# STM32F050F_Base.net
KiCad netlist of a schematic drawn in EAGLE
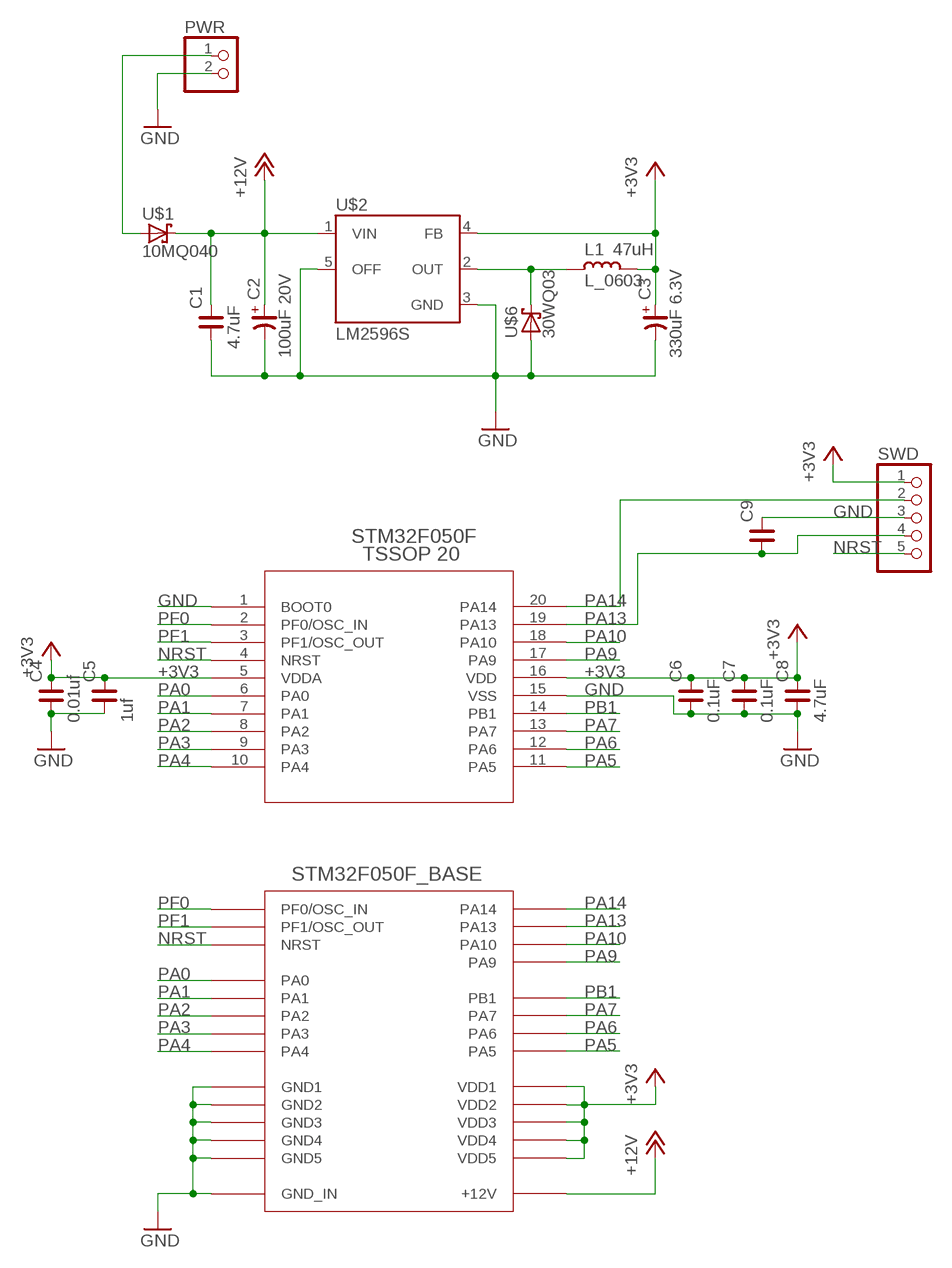
[diagram p0: schematic, sheet 1]

(export (version "E")
  (design (tool "Eeschema 10.0.6"))
  (components
    (comp (ref "C1")
      (value "4.7uF")
      (footprint "eagle-import:C1206")
      (libsource (lib "eagle-import") (part "C_1206"))
    )
    (comp (ref "C2")
      (value "100uF 20V")
      (footprint "eagle-import:C7343_T")
      (libsource (lib "eagle-import") (part "CP_7343"))
    )
    (comp (ref "C3")
      (value "330uF 6.3V")
      (footprint "eagle-import:C7343_T")
      (libsource (lib "eagle-import") (part "CP_7343"))
    )
    (comp (ref "C4")
      (value "0.01uf")
      (footprint "eagle-import:C0805")
      (libsource (lib "eagle-import") (part "C_0805"))
    )
    (comp (ref "C5")
      (value "1uf")
      (footprint "eagle-import:C0805")
      (libsource (lib "eagle-import") (part "C_0805"))
    )
    (comp (ref "C6")
      (value "0.1uF")
      (footprint "eagle-import:C0805")
      (libsource (lib "eagle-import") (part "C_0805"))
    )
    (comp (ref "C7")
      (value "0.1uF")
      (footprint "eagle-import:C0805")
      (libsource (lib "eagle-import") (part "C_0805"))
    )
    (comp (ref "C8")
      (value "4.7uF")
      (footprint "eagle-import:C1206")
      (libsource (lib "eagle-import") (part "C_1206"))
    )
    (comp (ref "C9")
      (value "C_1206")
      (footprint "eagle-import:C1206")
      (libsource (lib "eagle-import") (part "C_1206"))
    )
    (comp (ref "L1")
      (value "L_0603")
      (footprint "eagle-import:L0603")
      (fields (field (name "LCN0603T-47NJ-N") "47uH"))
      (libsource (lib "eagle-import") (part "L_0603"))
    )
    (comp (ref "PWR")
      (value "PINHD-1X02_2.54-90°-S")
      (footprint "eagle-import:1X02_90-S")
      (libsource (lib "eagle-import") (part "PINHD-1X02_2.54-90°-S"))
    )
    (comp (ref "SWD")
      (value "PINHD-1X05_2.54-90°-S")
      (footprint "eagle-import:1X05_90-S")
      (libsource (lib "eagle-import") (part "PINHD-1X05_2.54-90°-S"))
    )
    (comp (ref "U$1")
      (value "10MQ040")
      (footprint "eagle-import:SMA")
      (libsource (lib "eagle-import") (part "10MQ040"))
    )
    (comp (ref "U$2")
      (value "LM2596S")
      (footprint "eagle-import:TO263-5")
      (libsource (lib "eagle-import") (part "LM2596S"))
    )
    (comp (ref "U$4")
      (value "STM32F050F4P6")
      (footprint "eagle-import:TSSOP20")
      (libsource (lib "eagle-import") (part "STM32F050F4P6"))
    )
    (comp (ref "U$5")
      (value "STM32F050F_BASE_BASE")
      (footprint "eagle-import:STM32_BASE")
      (libsource (lib "eagle-import") (part "STM32F050F_BASE_BASE"))
    )
    (comp (ref "U$6")
      (value "30WQ03")
      (footprint "eagle-import:TO252")
      (libsource (lib "eagle-import") (part "30WQ03"))
    )
  )
  (nets
    (net (code "1") (name "+3V3") (class "Default")
      (node (ref "C3") (pin "+") (pinfunction "+_+") (pintype "passive"))
      (node (ref "C4") (pin "2") (pinfunction "2_2") (pintype "passive"))
      (node (ref "C5") (pin "2") (pinfunction "2_2") (pintype "passive"))
      (node (ref "C6") (pin "2") (pinfunction "2_2") (pintype "passive"))
      (node (ref "C7") (pin "2") (pinfunction "2_2") (pintype "passive"))
      (node (ref "C8") (pin "2") (pinfunction "2_2") (pintype "passive"))
      (node (ref "L1") (pin "1") (pinfunction "1_1") (pintype "passive"))
      (node (ref "SWD") (pin "1") (pinfunction "1_1") (pintype "passive"))
      (node (ref "U$2") (pin "4") (pinfunction "FB_4") (pintype "input"))
      (node (ref "U$4") (pin "16") (pinfunction "VDD_16") (pintype "passive"))
      (node (ref "U$4") (pin "5") (pinfunction "VDDA_5") (pintype "passive"))
      (node (ref "U$5") (pin "VDD1") (pinfunction "VDD1_VDD1") (pintype "passive"))
      (node (ref "U$5") (pin "VDD2") (pinfunction "VDD2_VDD2") (pintype "passive"))
      (node (ref "U$5") (pin "VDD3") (pinfunction "VDD3_VDD3") (pintype "passive"))
      (node (ref "U$5") (pin "VDD4") (pinfunction "VDD4_VDD4") (pintype "passive"))
      (node (ref "U$5") (pin "VDD5") (pinfunction "VDD5_VDD5") (pintype "passive"))
    )
    (net (code "2") (name "+12V") (class "Default")
      (node (ref "C1") (pin "2") (pinfunction "2_2") (pintype "passive"))
      (node (ref "C2") (pin "+") (pinfunction "+_+") (pintype "passive"))
      (node (ref "U$1") (pin "C") (pinfunction "C_C") (pintype "passive"))
      (node (ref "U$2") (pin "1") (pinfunction "VIN_1") (pintype "power_in"))
      (node (ref "U$5") (pin "+12V") (pinfunction "+12V_+12V") (pintype "passive"))
    )
    (net (code "3") (name "/NRST") (class "Default")
      (node (ref "SWD") (pin "5") (pinfunction "5_5") (pintype "passive"))
      (node (ref "U$4") (pin "4") (pinfunction "NRST_4") (pintype "passive"))
      (node (ref "U$5") (pin "NRST") (pinfunction "NRST_NRST") (pintype "passive"))
    )
    (net (code "4") (name "/PA0") (class "Default")
      (node (ref "U$4") (pin "6") (pinfunction "PA0_6") (pintype "passive"))
      (node (ref "U$5") (pin "PA0") (pinfunction "PA0_PA0") (pintype "passive"))
    )
    (net (code "5") (name "/PA1") (class "Default")
      (node (ref "U$4") (pin "7") (pinfunction "PA1_7") (pintype "passive"))
      (node (ref "U$5") (pin "PA1") (pinfunction "PA1_PA1") (pintype "passive"))
    )
    (net (code "6") (name "/PA2") (class "Default")
      (node (ref "U$4") (pin "8") (pinfunction "PA2_8") (pintype "passive"))
      (node (ref "U$5") (pin "PA2") (pinfunction "PA2_PA2") (pintype "passive"))
    )
    (net (code "7") (name "/PA3") (class "Default")
      (node (ref "U$4") (pin "9") (pinfunction "PA3_9") (pintype "passive"))
      (node (ref "U$5") (pin "PA3") (pinfunction "PA3_PA3") (pintype "passive"))
    )
    (net (code "8") (name "/PA4") (class "Default")
      (node (ref "U$4") (pin "10") (pinfunction "PA4_10") (pintype "passive"))
      (node (ref "U$5") (pin "PA4") (pinfunction "PA4_PA4") (pintype "passive"))
    )
    (net (code "9") (name "/PA5") (class "Default")
      (node (ref "U$4") (pin "11") (pinfunction "PA5_11") (pintype "passive"))
      (node (ref "U$5") (pin "PA5") (pinfunction "PA5_PA5") (pintype "passive"))
    )
    (net (code "10") (name "/PA6") (class "Default")
      (node (ref "U$4") (pin "12") (pinfunction "PA6_12") (pintype "passive"))
      (node (ref "U$5") (pin "PA6") (pinfunction "PA6_PA6") (pintype "passive"))
    )
    (net (code "11") (name "/PA7") (class "Default")
      (node (ref "U$4") (pin "13") (pinfunction "PA7_13") (pintype "passive"))
      (node (ref "U$5") (pin "PA7") (pinfunction "PA7_PA7") (pintype "passive"))
    )
    (net (code "12") (name "/PA9") (class "Default")
      (node (ref "U$4") (pin "17") (pinfunction "PA9_17") (pintype "passive"))
      (node (ref "U$5") (pin "PA9") (pinfunction "PA9_PA9") (pintype "passive"))
    )
    (net (code "13") (name "/PA10") (class "Default")
      (node (ref "U$4") (pin "18") (pinfunction "PA10_18") (pintype "passive"))
      (node (ref "U$5") (pin "PA10") (pinfunction "PA10_PA10") (pintype "passive"))
    )
    (net (code "14") (name "/PA13") (class "Default")
      (node (ref "C9") (pin "1") (pinfunction "1_1") (pintype "passive"))
      (node (ref "SWD") (pin "4") (pinfunction "4_4") (pintype "passive"))
      (node (ref "U$4") (pin "19") (pinfunction "PA13_19") (pintype "passive"))
      (node (ref "U$5") (pin "PA13") (pinfunction "PA13_PA13") (pintype "passive"))
    )
    (net (code "15") (name "/PA14") (class "Default")
      (node (ref "SWD") (pin "2") (pinfunction "2_2") (pintype "passive"))
      (node (ref "U$4") (pin "20") (pinfunction "PA14_20") (pintype "passive"))
      (node (ref "U$5") (pin "PA14") (pinfunction "PA14_PA14") (pintype "passive"))
    )
    (net (code "16") (name "/PB1") (class "Default")
      (node (ref "U$4") (pin "14") (pinfunction "PB1_14") (pintype "passive"))
      (node (ref "U$5") (pin "PB1") (pinfunction "PB1_PB1") (pintype "passive"))
    )
    (net (code "17") (name "/PF0") (class "Default")
      (node (ref "U$4") (pin "2") (pinfunction "PF0/OSC_IN_2") (pintype "passive"))
      (node (ref "U$5") (pin "PF0") (pinfunction "PF0/OSC_IN_PF0") (pintype "passive"))
    )
    (net (code "18") (name "/PF1") (class "Default")
      (node (ref "U$4") (pin "3") (pinfunction "PF1/OSC_OUT_3") (pintype "passive"))
      (node (ref "U$5") (pin "PF1") (pinfunction "PF1/OSC_OUT_PF1") (pintype "passive"))
    )
    (net (code "19") (name "GND") (class "Default")
      (node (ref "C1") (pin "1") (pinfunction "1_1") (pintype "passive"))
      (node (ref "C2") (pin "-") (pinfunction "-_-") (pintype "passive"))
      (node (ref "C3") (pin "-") (pinfunction "-_-") (pintype "passive"))
      (node (ref "C4") (pin "1") (pinfunction "1_1") (pintype "passive"))
      (node (ref "C5") (pin "1") (pinfunction "1_1") (pintype "passive"))
      (node (ref "C6") (pin "1") (pinfunction "1_1") (pintype "passive"))
      (node (ref "C7") (pin "1") (pinfunction "1_1") (pintype "passive"))
      (node (ref "C8") (pin "1") (pinfunction "1_1") (pintype "passive"))
      (node (ref "C9") (pin "2") (pinfunction "2_2") (pintype "passive"))
      (node (ref "PWR") (pin "2") (pinfunction "2_2") (pintype "passive"))
      (node (ref "SWD") (pin "3") (pinfunction "3_3") (pintype "passive"))
      (node (ref "U$2") (pin "3") (pinfunction "GND_3") (pintype "power_in"))
      (node (ref "U$2") (pin "5") (pinfunction "OFF_5") (pintype "input"))
      (node (ref "U$4") (pin "1") (pinfunction "BOOT0_1") (pintype "passive"))
      (node (ref "U$4") (pin "15") (pinfunction "VSS_15") (pintype "passive"))
      (node (ref "U$5") (pin "GND1") (pinfunction "GND1_GND1") (pintype "passive"))
      (node (ref "U$5") (pin "GND2") (pinfunction "GND2_GND2") (pintype "passive"))
      (node (ref "U$5") (pin "GND3") (pinfunction "GND3_GND3") (pintype "passive"))
      (node (ref "U$5") (pin "GND4") (pinfunction "GND4_GND4") (pintype "passive"))
      (node (ref "U$5") (pin "GND5") (pinfunction "GND5_GND5") (pintype "passive"))
      (node (ref "U$5") (pin "GND_IN") (pinfunction "GND_IN_GND_IN") (pintype "passive"))
      (node (ref "U$6") (pin "1") (pinfunction "A_1") (pintype "passive"))
      (node (ref "U$6") (pin "2") (pinfunction "A_2") (pintype "passive"))
    )
    (net (code "20") (name "Net-(PWR-Pad1)") (class "Default")
      (node (ref "PWR") (pin "1") (pinfunction "1_1") (pintype "passive"))
      (node (ref "U$1") (pin "A") (pinfunction "A_A") (pintype "passive"))
    )
    (net (code "21") (name "Net-(U$2-OUT)") (class "Default")
      (node (ref "L1") (pin "2") (pinfunction "2_2") (pintype "passive"))
      (node (ref "U$2") (pin "2") (pinfunction "OUT_2") (pintype "output"))
      (node (ref "U$6") (pin "3") (pinfunction "C_3") (pintype "passive"))
    )
  )
)
